# XC6SLX09-2FTG256C.net
KiCad netlist of a schematic drawn in Altium Designer
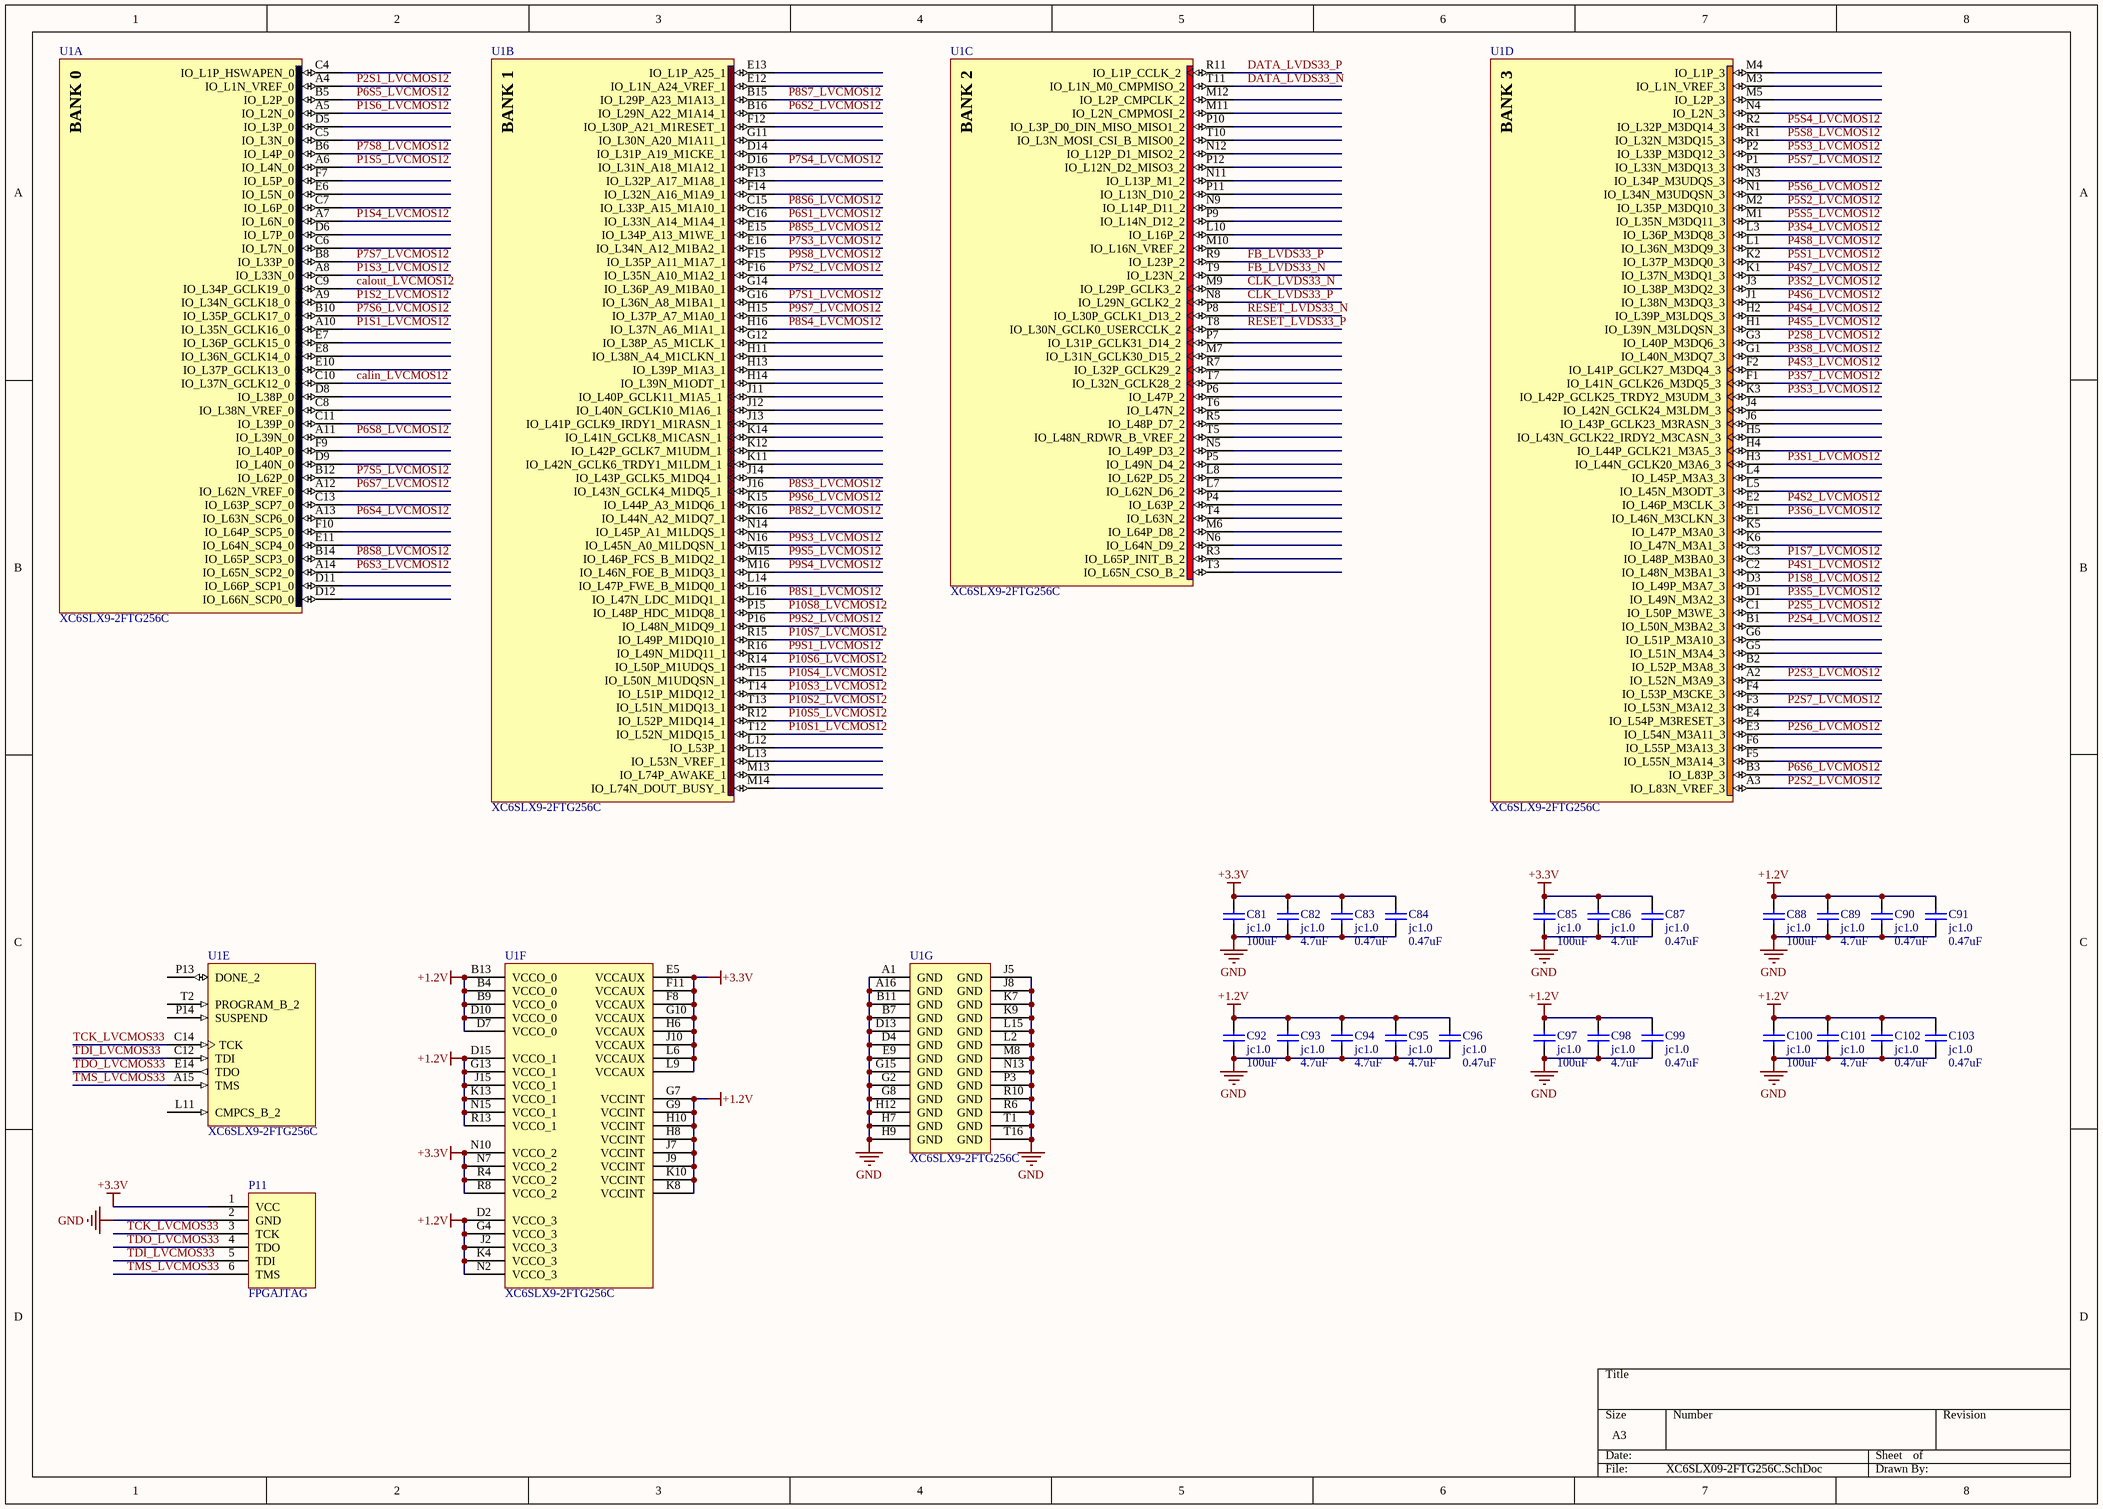
[diagram p0: XC6SLX09-2FTG256C.SchDoc]

(export (version "E")
  (design (tool "Eeschema 10.0.6"))
  (components
    (comp (ref "C81")
      (value "jc1.0")
      (footprint "0805")
      (description "Capacitor")
      (fields (field (name "ALTIUM_VALUE") "100uF") (field (name "PUBLISHER") "Altium Limited"))
      (libsource (lib "LIB01DXP2006SchLib") (part "Cap"))
    )
    (comp (ref "C82")
      (value "jc1.0")
      (footprint "0402")
      (description "Capacitor")
      (fields (field (name "ALTIUM_VALUE") "4.7uF") (field (name "PUBLISHER") "Altium Limited"))
      (libsource (lib "LIB01DXP2006SchLib") (part "Cap"))
    )
    (comp (ref "C83")
      (value "jc1.0")
      (footprint "0402")
      (description "Capacitor")
      (fields (field (name "ALTIUM_VALUE") "0.47uF") (field (name "PUBLISHER") "Altium Limited"))
      (libsource (lib "LIB01DXP2006SchLib") (part "Cap"))
    )
    (comp (ref "C84")
      (value "jc1.0")
      (footprint "0402")
      (description "Capacitor")
      (fields (field (name "ALTIUM_VALUE") "0.47uF") (field (name "PUBLISHER") "Altium Limited"))
      (libsource (lib "LIB01DXP2006SchLib") (part "Cap"))
    )
    (comp (ref "C85")
      (value "jc1.0")
      (footprint "0805")
      (description "Capacitor")
      (fields (field (name "ALTIUM_VALUE") "100uF") (field (name "PUBLISHER") "Altium Limited"))
      (libsource (lib "LIB01DXP2006SchLib") (part "Cap"))
    )
    (comp (ref "C86")
      (value "jc1.0")
      (footprint "0402")
      (description "Capacitor")
      (fields (field (name "ALTIUM_VALUE") "4.7uF") (field (name "PUBLISHER") "Altium Limited"))
      (libsource (lib "LIB01DXP2006SchLib") (part "Cap"))
    )
    (comp (ref "C87")
      (value "jc1.0")
      (footprint "0402")
      (description "Capacitor")
      (fields (field (name "ALTIUM_VALUE") "0.47uF") (field (name "PUBLISHER") "Altium Limited"))
      (libsource (lib "LIB01DXP2006SchLib") (part "Cap"))
    )
    (comp (ref "C88")
      (value "jc1.0")
      (footprint "0805")
      (description "Capacitor")
      (fields (field (name "ALTIUM_VALUE") "100uF") (field (name "PUBLISHER") "Altium Limited"))
      (libsource (lib "LIB01DXP2006SchLib") (part "Cap"))
    )
    (comp (ref "C89")
      (value "jc1.0")
      (footprint "0402")
      (description "Capacitor")
      (fields (field (name "ALTIUM_VALUE") "4.7uF") (field (name "PUBLISHER") "Altium Limited"))
      (libsource (lib "LIB01DXP2006SchLib") (part "Cap"))
    )
    (comp (ref "C90")
      (value "jc1.0")
      (footprint "0402")
      (description "Capacitor")
      (fields (field (name "ALTIUM_VALUE") "0.47uF") (field (name "PUBLISHER") "Altium Limited"))
      (libsource (lib "LIB01DXP2006SchLib") (part "Cap"))
    )
    (comp (ref "C91")
      (value "jc1.0")
      (footprint "0402")
      (description "Capacitor")
      (fields (field (name "ALTIUM_VALUE") "0.47uF") (field (name "PUBLISHER") "Altium Limited"))
      (libsource (lib "LIB01DXP2006SchLib") (part "Cap"))
    )
    (comp (ref "C92")
      (value "jc1.0")
      (footprint "0805")
      (description "Capacitor")
      (fields (field (name "ALTIUM_VALUE") "100uF") (field (name "PUBLISHER") "Altium Limited"))
      (libsource (lib "LIB01DXP2006SchLib") (part "Cap"))
    )
    (comp (ref "C93")
      (value "jc1.0")
      (footprint "0402")
      (description "Capacitor")
      (fields (field (name "ALTIUM_VALUE") "4.7uF") (field (name "PUBLISHER") "Altium Limited"))
      (libsource (lib "LIB01DXP2006SchLib") (part "Cap"))
    )
    (comp (ref "C94")
      (value "jc1.0")
      (footprint "0402")
      (description "Capacitor")
      (fields (field (name "ALTIUM_VALUE") "4.7uF") (field (name "PUBLISHER") "Altium Limited"))
      (libsource (lib "LIB01DXP2006SchLib") (part "Cap"))
    )
    (comp (ref "C95")
      (value "jc1.0")
      (footprint "0402")
      (description "Capacitor")
      (fields (field (name "ALTIUM_VALUE") "4.7uF") (field (name "PUBLISHER") "Altium Limited"))
      (libsource (lib "LIB01DXP2006SchLib") (part "Cap"))
    )
    (comp (ref "C96")
      (value "jc1.0")
      (footprint "0402")
      (description "Capacitor")
      (fields (field (name "ALTIUM_VALUE") "0.47uF") (field (name "PUBLISHER") "Altium Limited"))
      (libsource (lib "LIB01DXP2006SchLib") (part "Cap"))
    )
    (comp (ref "C97")
      (value "jc1.0")
      (footprint "0805")
      (description "Capacitor")
      (fields (field (name "ALTIUM_VALUE") "100uF") (field (name "PUBLISHER") "Altium Limited"))
      (libsource (lib "LIB01DXP2006SchLib") (part "Cap"))
    )
    (comp (ref "C98")
      (value "jc1.0")
      (footprint "0402")
      (description "Capacitor")
      (fields (field (name "ALTIUM_VALUE") "4.7uF") (field (name "PUBLISHER") "Altium Limited"))
      (libsource (lib "LIB01DXP2006SchLib") (part "Cap"))
    )
    (comp (ref "C99")
      (value "jc1.0")
      (footprint "0402")
      (description "Capacitor")
      (fields (field (name "ALTIUM_VALUE") "0.47uF") (field (name "PUBLISHER") "Altium Limited"))
      (libsource (lib "LIB01DXP2006SchLib") (part "Cap"))
    )
    (comp (ref "C100")
      (value "jc1.0")
      (footprint "0805")
      (description "Capacitor")
      (fields (field (name "ALTIUM_VALUE") "100uF") (field (name "PUBLISHER") "Altium Limited"))
      (libsource (lib "LIB01DXP2006SchLib") (part "Cap"))
    )
    (comp (ref "C101")
      (value "jc1.0")
      (footprint "0402")
      (description "Capacitor")
      (fields (field (name "ALTIUM_VALUE") "4.7uF") (field (name "PUBLISHER") "Altium Limited"))
      (libsource (lib "LIB01DXP2006SchLib") (part "Cap"))
    )
    (comp (ref "C102")
      (value "jc1.0")
      (footprint "0402")
      (description "Capacitor")
      (fields (field (name "ALTIUM_VALUE") "0.47uF") (field (name "PUBLISHER") "Altium Limited"))
      (libsource (lib "LIB01DXP2006SchLib") (part "Cap"))
    )
    (comp (ref "C103")
      (value "jc1.0")
      (footprint "0402")
      (description "Capacitor")
      (fields (field (name "ALTIUM_VALUE") "0.47uF") (field (name "PUBLISHER") "Altium Limited"))
      (libsource (lib "LIB01DXP2006SchLib") (part "Cap"))
    )
    (comp (ref "P11")
      (value "FPGAJTAG")
      (footprint "SIP6")
      (libsource (lib "LIB01DXP2006SchLib") (part "FPGAJTAGHEADER"))
    )
    (comp (ref "U1")
      (value "XC6SLX9-2FTG256C")
      (footprint "FTG256")
      (libsource (lib "Spartan-6") (part "XC6SLX9-2FTG256C"))
    )
  )
  (nets
    (net (code "1") (name "+1.2V") (class "Default")
      (node (ref "C100") (pin "2") (pinfunction "2_2") (pintype "passive"))
      (node (ref "C101") (pin "2") (pinfunction "2_2") (pintype "passive"))
      (node (ref "C102") (pin "2") (pinfunction "2_2") (pintype "passive"))
      (node (ref "C103") (pin "2") (pinfunction "2_2") (pintype "passive"))
      (node (ref "C88") (pin "2") (pinfunction "2_2") (pintype "passive"))
      (node (ref "C89") (pin "2") (pinfunction "2_2") (pintype "passive"))
      (node (ref "C90") (pin "2") (pinfunction "2_2") (pintype "passive"))
      (node (ref "C91") (pin "2") (pinfunction "2_2") (pintype "passive"))
      (node (ref "C92") (pin "2") (pinfunction "2_2") (pintype "passive"))
      (node (ref "C93") (pin "2") (pinfunction "2_2") (pintype "passive"))
      (node (ref "C94") (pin "2") (pinfunction "2_2") (pintype "passive"))
      (node (ref "C95") (pin "2") (pinfunction "2_2") (pintype "passive"))
      (node (ref "C96") (pin "2") (pinfunction "2_2") (pintype "passive"))
      (node (ref "C97") (pin "2") (pinfunction "2_2") (pintype "passive"))
      (node (ref "C98") (pin "2") (pinfunction "2_2") (pintype "passive"))
      (node (ref "C99") (pin "2") (pinfunction "2_2") (pintype "passive"))
      (node (ref "U1") (pin "B13") (pinfunction "VCCO_0_B13") (pintype "power_in"))
      (node (ref "U1") (pin "B4") (pinfunction "VCCO_0_B4") (pintype "power_in"))
      (node (ref "U1") (pin "B9") (pinfunction "VCCO_0_B9") (pintype "power_in"))
      (node (ref "U1") (pin "D10") (pinfunction "VCCO_0_D10") (pintype "power_in"))
      (node (ref "U1") (pin "D15") (pinfunction "VCCO_1_D15") (pintype "power_in"))
      (node (ref "U1") (pin "D2") (pinfunction "VCCO_3_D2") (pintype "power_in"))
      (node (ref "U1") (pin "D7") (pinfunction "VCCO_0_D7") (pintype "power_in"))
      (node (ref "U1") (pin "G13") (pinfunction "VCCO_1_G13") (pintype "power_in"))
      (node (ref "U1") (pin "G4") (pinfunction "VCCO_3_G4") (pintype "power_in"))
      (node (ref "U1") (pin "G7") (pinfunction "VCCINT_G7") (pintype "power_in"))
      (node (ref "U1") (pin "G9") (pinfunction "VCCINT_G9") (pintype "power_in"))
      (node (ref "U1") (pin "H10") (pinfunction "VCCINT_H10") (pintype "power_in"))
      (node (ref "U1") (pin "H8") (pinfunction "VCCINT_H8") (pintype "power_in"))
      (node (ref "U1") (pin "J15") (pinfunction "VCCO_1_J15") (pintype "power_in"))
      (node (ref "U1") (pin "J2") (pinfunction "VCCO_3_J2") (pintype "power_in"))
      (node (ref "U1") (pin "J7") (pinfunction "VCCINT_J7") (pintype "power_in"))
      (node (ref "U1") (pin "J9") (pinfunction "VCCINT_J9") (pintype "power_in"))
      (node (ref "U1") (pin "K10") (pinfunction "VCCINT_K10") (pintype "power_in"))
      (node (ref "U1") (pin "K13") (pinfunction "VCCO_1_K13") (pintype "power_in"))
      (node (ref "U1") (pin "K4") (pinfunction "VCCO_3_K4") (pintype "power_in"))
      (node (ref "U1") (pin "K8") (pinfunction "VCCINT_K8") (pintype "power_in"))
      (node (ref "U1") (pin "N15") (pinfunction "VCCO_1_N15") (pintype "power_in"))
      (node (ref "U1") (pin "N2") (pinfunction "VCCO_3_N2") (pintype "power_in"))
      (node (ref "U1") (pin "R13") (pinfunction "VCCO_1_R13") (pintype "power_in"))
    )
    (net (code "2") (name "+3.3V") (class "Default")
      (node (ref "C81") (pin "2") (pinfunction "2_2") (pintype "passive"))
      (node (ref "C82") (pin "2") (pinfunction "2_2") (pintype "passive"))
      (node (ref "C83") (pin "2") (pinfunction "2_2") (pintype "passive"))
      (node (ref "C84") (pin "2") (pinfunction "2_2") (pintype "passive"))
      (node (ref "C85") (pin "2") (pinfunction "2_2") (pintype "passive"))
      (node (ref "C86") (pin "2") (pinfunction "2_2") (pintype "passive"))
      (node (ref "C87") (pin "2") (pinfunction "2_2") (pintype "passive"))
      (node (ref "P11") (pin "1") (pinfunction "VCC_1") (pintype "passive"))
      (node (ref "U1") (pin "E5") (pinfunction "VCCAUX_E5") (pintype "power_in"))
      (node (ref "U1") (pin "F11") (pinfunction "VCCAUX_F11") (pintype "power_in"))
      (node (ref "U1") (pin "F8") (pinfunction "VCCAUX_F8") (pintype "power_in"))
      (node (ref "U1") (pin "G10") (pinfunction "VCCAUX_G10") (pintype "power_in"))
      (node (ref "U1") (pin "H6") (pinfunction "VCCAUX_H6") (pintype "power_in"))
      (node (ref "U1") (pin "J10") (pinfunction "VCCAUX_J10") (pintype "power_in"))
      (node (ref "U1") (pin "L6") (pinfunction "VCCAUX_L6") (pintype "power_in"))
      (node (ref "U1") (pin "L9") (pinfunction "VCCAUX_L9") (pintype "power_in"))
      (node (ref "U1") (pin "N10") (pinfunction "VCCO_2_N10") (pintype "power_in"))
      (node (ref "U1") (pin "N7") (pinfunction "VCCO_2_N7") (pintype "power_in"))
      (node (ref "U1") (pin "R4") (pinfunction "VCCO_2_R4") (pintype "power_in"))
      (node (ref "U1") (pin "R8") (pinfunction "VCCO_2_R8") (pintype "power_in"))
    )
    (net (code "3") (name "/CLK_LVDS33_N") (class "Default")
      (node (ref "U1") (pin "M9") (pinfunction "IO_L29P_GCLK3_2_M9") (pintype "bidirectional"))
    )
    (net (code "4") (name "/CLK_LVDS33_P") (class "Default")
      (node (ref "U1") (pin "N8") (pinfunction "IO_L29N_GCLK2_2_N8") (pintype "bidirectional"))
    )
    (net (code "5") (name "/DATA_LVDS33_N") (class "Default")
      (node (ref "U1") (pin "T11") (pinfunction "IO_L1N_M0_CMPMISO_2_T11") (pintype "bidirectional"))
    )
    (net (code "6") (name "/DATA_LVDS33_P") (class "Default")
      (node (ref "U1") (pin "R11") (pinfunction "IO_L1P_CCLK_2_R11") (pintype "bidirectional"))
    )
    (net (code "7") (name "/FB_LVDS33_N") (class "Default")
      (node (ref "U1") (pin "T9") (pinfunction "IO_L23N_2_T9") (pintype "bidirectional"))
    )
    (net (code "8") (name "/FB_LVDS33_P") (class "Default")
      (node (ref "U1") (pin "R9") (pinfunction "IO_L23P_2_R9") (pintype "bidirectional"))
    )
    (net (code "9") (name "/P1S1_LVCMOS12") (class "Default")
      (node (ref "U1") (pin "A10") (pinfunction "IO_L35N_GCLK16_0_A10") (pintype "bidirectional"))
    )
    (net (code "10") (name "/P1S2_LVCMOS12") (class "Default")
      (node (ref "U1") (pin "A9") (pinfunction "IO_L34N_GCLK18_0_A9") (pintype "bidirectional"))
    )
    (net (code "11") (name "/P1S3_LVCMOS12") (class "Default")
      (node (ref "U1") (pin "A8") (pinfunction "IO_L33N_0_A8") (pintype "bidirectional"))
    )
    (net (code "12") (name "/P1S4_LVCMOS12") (class "Default")
      (node (ref "U1") (pin "A7") (pinfunction "IO_L6N_0_A7") (pintype "bidirectional"))
    )
    (net (code "13") (name "/P1S5_LVCMOS12") (class "Default")
      (node (ref "U1") (pin "A6") (pinfunction "IO_L4N_0_A6") (pintype "bidirectional"))
    )
    (net (code "14") (name "/P1S6_LVCMOS12") (class "Default")
      (node (ref "U1") (pin "A5") (pinfunction "IO_L2N_0_A5") (pintype "bidirectional"))
    )
    (net (code "15") (name "/P1S7_LVCMOS12") (class "Default")
      (node (ref "U1") (pin "C3") (pinfunction "IO_L48P_M3BA0_3_C3") (pintype "bidirectional"))
    )
    (net (code "16") (name "/P1S8_LVCMOS12") (class "Default")
      (node (ref "U1") (pin "D3") (pinfunction "IO_L49P_M3A7_3_D3") (pintype "bidirectional"))
    )
    (net (code "17") (name "/P2S1_LVCMOS12") (class "Default")
      (node (ref "U1") (pin "A4") (pinfunction "IO_L1N_VREF_0_A4") (pintype "bidirectional"))
    )
    (net (code "18") (name "/P2S2_LVCMOS12") (class "Default")
      (node (ref "U1") (pin "A3") (pinfunction "IO_L83N_VREF_3_A3") (pintype "bidirectional"))
    )
    (net (code "19") (name "/P2S3_LVCMOS12") (class "Default")
      (node (ref "U1") (pin "A2") (pinfunction "IO_L52N_M3A9_3_A2") (pintype "bidirectional"))
    )
    (net (code "20") (name "/P2S4_LVCMOS12") (class "Default")
      (node (ref "U1") (pin "B1") (pinfunction "IO_L50N_M3BA2_3_B1") (pintype "bidirectional"))
    )
    (net (code "21") (name "/P2S5_LVCMOS12") (class "Default")
      (node (ref "U1") (pin "C1") (pinfunction "IO_L50P_M3WE_3_C1") (pintype "bidirectional"))
    )
    (net (code "22") (name "/P2S6_LVCMOS12") (class "Default")
      (node (ref "U1") (pin "E3") (pinfunction "IO_L54N_M3A11_3_E3") (pintype "bidirectional"))
    )
    (net (code "23") (name "/P2S7_LVCMOS12") (class "Default")
      (node (ref "U1") (pin "F3") (pinfunction "IO_L53N_M3A12_3_F3") (pintype "bidirectional"))
    )
    (net (code "24") (name "/P2S8_LVCMOS12") (class "Default")
      (node (ref "U1") (pin "G3") (pinfunction "IO_L40P_M3DQ6_3_G3") (pintype "bidirectional"))
    )
    (net (code "25") (name "/P3S1_LVCMOS12") (class "Default")
      (node (ref "U1") (pin "H3") (pinfunction "IO_L44N_GCLK20_M3A6_3_H3") (pintype "bidirectional"))
    )
    (net (code "26") (name "/P3S2_LVCMOS12") (class "Default")
      (node (ref "U1") (pin "J3") (pinfunction "IO_L38P_M3DQ2_3_J3") (pintype "bidirectional"))
    )
    (net (code "27") (name "/P3S3_LVCMOS12") (class "Default")
      (node (ref "U1") (pin "K3") (pinfunction "IO_L42P_GCLK25_TRDY2_M3UDM_3_K3") (pintype "bidirectional"))
    )
    (net (code "28") (name "/P3S4_LVCMOS12") (class "Default")
      (node (ref "U1") (pin "L3") (pinfunction "IO_L36P_M3DQ8_3_L3") (pintype "bidirectional"))
    )
    (net (code "29") (name "/P3S5_LVCMOS12") (class "Default")
      (node (ref "U1") (pin "D1") (pinfunction "IO_L49N_M3A2_3_D1") (pintype "bidirectional"))
    )
    (net (code "30") (name "/P3S6_LVCMOS12") (class "Default")
      (node (ref "U1") (pin "E1") (pinfunction "IO_L46N_M3CLKN_3_E1") (pintype "bidirectional"))
    )
    (net (code "31") (name "/P3S7_LVCMOS12") (class "Default")
      (node (ref "U1") (pin "F1") (pinfunction "IO_L41N_GCLK26_M3DQ5_3_F1") (pintype "bidirectional"))
    )
    (net (code "32") (name "/P3S8_LVCMOS12") (class "Default")
      (node (ref "U1") (pin "G1") (pinfunction "IO_L40N_M3DQ7_3_G1") (pintype "bidirectional"))
    )
    (net (code "33") (name "/P4S1_LVCMOS12") (class "Default")
      (node (ref "U1") (pin "C2") (pinfunction "IO_L48N_M3BA1_3_C2") (pintype "bidirectional"))
    )
    (net (code "34") (name "/P4S2_LVCMOS12") (class "Default")
      (node (ref "U1") (pin "E2") (pinfunction "IO_L46P_M3CLK_3_E2") (pintype "bidirectional"))
    )
    (net (code "35") (name "/P4S3_LVCMOS12") (class "Default")
      (node (ref "U1") (pin "F2") (pinfunction "IO_L41P_GCLK27_M3DQ4_3_F2") (pintype "bidirectional"))
    )
    (net (code "36") (name "/P4S4_LVCMOS12") (class "Default")
      (node (ref "U1") (pin "H2") (pinfunction "IO_L39P_M3LDQS_3_H2") (pintype "bidirectional"))
    )
    (net (code "37") (name "/P4S5_LVCMOS12") (class "Default")
      (node (ref "U1") (pin "H1") (pinfunction "IO_L39N_M3LDQSN_3_H1") (pintype "bidirectional"))
    )
    (net (code "38") (name "/P4S6_LVCMOS12") (class "Default")
      (node (ref "U1") (pin "J1") (pinfunction "IO_L38N_M3DQ3_3_J1") (pintype "bidirectional"))
    )
    (net (code "39") (name "/P4S7_LVCMOS12") (class "Default")
      (node (ref "U1") (pin "K1") (pinfunction "IO_L37N_M3DQ1_3_K1") (pintype "bidirectional"))
    )
    (net (code "40") (name "/P4S8_LVCMOS12") (class "Default")
      (node (ref "U1") (pin "L1") (pinfunction "IO_L36N_M3DQ9_3_L1") (pintype "bidirectional"))
    )
    (net (code "41") (name "/P5S1_LVCMOS12") (class "Default")
      (node (ref "U1") (pin "K2") (pinfunction "IO_L37P_M3DQ0_3_K2") (pintype "bidirectional"))
    )
    (net (code "42") (name "/P5S2_LVCMOS12") (class "Default")
      (node (ref "U1") (pin "M2") (pinfunction "IO_L35P_M3DQ10_3_M2") (pintype "bidirectional"))
    )
    (net (code "43") (name "/P5S3_LVCMOS12") (class "Default")
      (node (ref "U1") (pin "P2") (pinfunction "IO_L33P_M3DQ12_3_P2") (pintype "bidirectional"))
    )
    (net (code "44") (name "/P5S4_LVCMOS12") (class "Default")
      (node (ref "U1") (pin "R2") (pinfunction "IO_L32P_M3DQ14_3_R2") (pintype "bidirectional"))
    )
    (net (code "45") (name "/P5S5_LVCMOS12") (class "Default")
      (node (ref "U1") (pin "M1") (pinfunction "IO_L35N_M3DQ11_3_M1") (pintype "bidirectional"))
    )
    (net (code "46") (name "/P5S6_LVCMOS12") (class "Default")
      (node (ref "U1") (pin "N1") (pinfunction "IO_L34N_M3UDQSN_3_N1") (pintype "bidirectional"))
    )
    (net (code "47") (name "/P5S7_LVCMOS12") (class "Default")
      (node (ref "U1") (pin "P1") (pinfunction "IO_L33N_M3DQ13_3_P1") (pintype "bidirectional"))
    )
    (net (code "48") (name "/P5S8_LVCMOS12") (class "Default")
      (node (ref "U1") (pin "R1") (pinfunction "IO_L32N_M3DQ15_3_R1") (pintype "bidirectional"))
    )
    (net (code "49") (name "/P6S1_LVCMOS12") (class "Default")
      (node (ref "U1") (pin "C16") (pinfunction "IO_L33N_A14_M1A4_1_C16") (pintype "bidirectional"))
    )
    (net (code "50") (name "/P6S2_LVCMOS12") (class "Default")
      (node (ref "U1") (pin "B16") (pinfunction "IO_L29N_A22_M1A14_1_B16") (pintype "bidirectional"))
    )
    (net (code "51") (name "/P6S3_LVCMOS12") (class "Default")
      (node (ref "U1") (pin "A14") (pinfunction "IO_L65N_SCP2_0_A14") (pintype "bidirectional"))
    )
    (net (code "52") (name "/P6S4_LVCMOS12") (class "Default")
      (node (ref "U1") (pin "A13") (pinfunction "IO_L63N_SCP6_0_A13") (pintype "bidirectional"))
    )
    (net (code "53") (name "/P6S5_LVCMOS12") (class "Default")
      (node (ref "U1") (pin "B5") (pinfunction "IO_L2P_0_B5") (pintype "bidirectional"))
    )
    (net (code "54") (name "/P6S6_LVCMOS12") (class "Default")
      (node (ref "U1") (pin "B3") (pinfunction "IO_L83P_3_B3") (pintype "bidirectional"))
    )
    (net (code "55") (name "/P6S7_LVCMOS12") (class "Default")
      (node (ref "U1") (pin "A12") (pinfunction "IO_L62N_VREF_0_A12") (pintype "bidirectional"))
    )
    (net (code "56") (name "/P6S8_LVCMOS12") (class "Default")
      (node (ref "U1") (pin "A11") (pinfunction "IO_L39N_0_A11") (pintype "bidirectional"))
    )
    (net (code "57") (name "/P7S1_LVCMOS12") (class "Default")
      (node (ref "U1") (pin "G16") (pinfunction "IO_L36N_A8_M1BA1_1_G16") (pintype "bidirectional"))
    )
    (net (code "58") (name "/P7S2_LVCMOS12") (class "Default")
      (node (ref "U1") (pin "F16") (pinfunction "IO_L35N_A10_M1A2_1_F16") (pintype "bidirectional"))
    )
    (net (code "59") (name "/P7S3_LVCMOS12") (class "Default")
      (node (ref "U1") (pin "E16") (pinfunction "IO_L34N_A12_M1BA2_1_E16") (pintype "bidirectional"))
    )
    (net (code "60") (name "/P7S4_LVCMOS12") (class "Default")
      (node (ref "U1") (pin "D16") (pinfunction "IO_L31N_A18_M1A12_1_D16") (pintype "bidirectional"))
    )
    (net (code "61") (name "/P7S5_LVCMOS12") (class "Default")
      (node (ref "U1") (pin "B12") (pinfunction "IO_L62P_0_B12") (pintype "bidirectional"))
    )
    (net (code "62") (name "/P7S6_LVCMOS12") (class "Default")
      (node (ref "U1") (pin "B10") (pinfunction "IO_L35P_GCLK17_0_B10") (pintype "bidirectional"))
    )
    (net (code "63") (name "/P7S7_LVCMOS12") (class "Default")
      (node (ref "U1") (pin "B8") (pinfunction "IO_L33P_0_B8") (pintype "bidirectional"))
    )
    (net (code "64") (name "/P7S8_LVCMOS12") (class "Default")
      (node (ref "U1") (pin "B6") (pinfunction "IO_L4P_0_B6") (pintype "bidirectional"))
    )
    (net (code "65") (name "/P8S1_LVCMOS12") (class "Default")
      (node (ref "U1") (pin "L16") (pinfunction "IO_L47N_LDC_M1DQ1_1_L16") (pintype "bidirectional"))
    )
    (net (code "66") (name "/P8S2_LVCMOS12") (class "Default")
      (node (ref "U1") (pin "K16") (pinfunction "IO_L44N_A2_M1DQ7_1_K16") (pintype "bidirectional"))
    )
    (net (code "67") (name "/P8S3_LVCMOS12") (class "Default")
      (node (ref "U1") (pin "J16") (pinfunction "IO_L43N_GCLK4_M1DQ5_1_J16") (pintype "bidirectional"))
    )
    (net (code "68") (name "/P8S4_LVCMOS12") (class "Default")
      (node (ref "U1") (pin "H16") (pinfunction "IO_L37N_A6_M1A1_1_H16") (pintype "bidirectional"))
    )
    (net (code "69") (name "/P8S5_LVCMOS12") (class "Default")
      (node (ref "U1") (pin "E15") (pinfunction "IO_L34P_A13_M1WE_1_E15") (pintype "bidirectional"))
    )
    (net (code "70") (name "/P8S6_LVCMOS12") (class "Default")
      (node (ref "U1") (pin "C15") (pinfunction "IO_L33P_A15_M1A10_1_C15") (pintype "bidirectional"))
    )
    (net (code "71") (name "/P8S7_LVCMOS12") (class "Default")
      (node (ref "U1") (pin "B15") (pinfunction "IO_L29P_A23_M1A13_1_B15") (pintype "bidirectional"))
    )
    (net (code "72") (name "/P8S8_LVCMOS12") (class "Default")
      (node (ref "U1") (pin "B14") (pinfunction "IO_L65P_SCP3_0_B14") (pintype "bidirectional"))
    )
    (net (code "73") (name "/P9S1_LVCMOS12") (class "Default")
      (node (ref "U1") (pin "R16") (pinfunction "IO_L49N_M1DQ11_1_R16") (pintype "bidirectional"))
    )
    (net (code "74") (name "/P9S2_LVCMOS12") (class "Default")
      (node (ref "U1") (pin "P16") (pinfunction "IO_L48N_M1DQ9_1_P16") (pintype "bidirectional"))
    )
    (net (code "75") (name "/P9S3_LVCMOS12") (class "Default")
      (node (ref "U1") (pin "N16") (pinfunction "IO_L45N_A0_M1LDQSN_1_N16") (pintype "bidirectional"))
    )
    (net (code "76") (name "/P9S4_LVCMOS12") (class "Default")
      (node (ref "U1") (pin "M16") (pinfunction "IO_L46N_FOE_B_M1DQ3_1_M16") (pintype "bidirectional"))
    )
    (net (code "77") (name "/P9S5_LVCMOS12") (class "Default")
      (node (ref "U1") (pin "M15") (pinfunction "IO_L46P_FCS_B_M1DQ2_1_M15") (pintype "bidirectional"))
    )
    (net (code "78") (name "/P9S6_LVCMOS12") (class "Default")
      (node (ref "U1") (pin "K15") (pinfunction "IO_L44P_A3_M1DQ6_1_K15") (pintype "bidirectional"))
    )
    (net (code "79") (name "/P9S7_LVCMOS12") (class "Default")
      (node (ref "U1") (pin "H15") (pinfunction "IO_L37P_A7_M1A0_1_H15") (pintype "bidirectional"))
    )
    (net (code "80") (name "/P9S8_LVCMOS12") (class "Default")
      (node (ref "U1") (pin "F15") (pinfunction "IO_L35P_A11_M1A7_1_F15") (pintype "bidirectional"))
    )
    (net (code "81") (name "/P10S1_LVCMOS12") (class "Default")
      (node (ref "U1") (pin "T12") (pinfunction "IO_L52N_M1DQ15_1_T12") (pintype "bidirectional"))
    )
    (net (code "82") (name "/P10S2_LVCMOS12") (class "Default")
      (node (ref "U1") (pin "T13") (pinfunction "IO_L51N_M1DQ13_1_T13") (pintype "bidirectional"))
    )
    (net (code "83") (name "/P10S3_LVCMOS12") (class "Default")
      (node (ref "U1") (pin "T14") (pinfunction "IO_L51P_M1DQ12_1_T14") (pintype "bidirectional"))
    )
    (net (code "84") (name "/P10S4_LVCMOS12") (class "Default")
      (node (ref "U1") (pin "T15") (pinfunction "IO_L50N_M1UDQSN_1_T15") (pintype "bidirectional"))
    )
    (net (code "85") (name "/P10S5_LVCMOS12") (class "Default")
      (node (ref "U1") (pin "R12") (pinfunction "IO_L52P_M1DQ14_1_R12") (pintype "bidirectional"))
    )
    (net (code "86") (name "/P10S6_LVCMOS12") (class "Default")
      (node (ref "U1") (pin "R14") (pinfunction "IO_L50P_M1UDQS_1_R14") (pintype "bidirectional"))
    )
    (net (code "87") (name "/P10S7_LVCMOS12") (class "Default")
      (node (ref "U1") (pin "R15") (pinfunction "IO_L49P_M1DQ10_1_R15") (pintype "bidirectional"))
    )
    (net (code "88") (name "/P10S8_LVCMOS12") (class "Default")
      (node (ref "U1") (pin "P15") (pinfunction "IO_L48P_HDC_M1DQ8_1_P15") (pintype "bidirectional"))
    )
    (net (code "89") (name "/RESET_LVDS33_N") (class "Default")
      (node (ref "U1") (pin "P8") (pinfunction "IO_L30P_GCLK1_D13_2_P8") (pintype "bidirectional"))
    )
    (net (code "90") (name "/RESET_LVDS33_P") (class "Default")
      (node (ref "U1") (pin "T8") (pinfunction "IO_L30N_GCLK0_USERCCLK_2_T8") (pintype "bidirectional"))
    )
    (net (code "91") (name "/TCK_LVCMOS33") (class "Default")
      (node (ref "P11") (pin "3") (pinfunction "TCK_3") (pintype "passive"))
      (node (ref "U1") (pin "C14") (pinfunction "TCK_C14") (pintype "input"))
    )
    (net (code "92") (name "/TDI_LVCMOS33") (class "Default")
      (node (ref "P11") (pin "5") (pinfunction "TDI_5") (pintype "passive"))
      (node (ref "U1") (pin "C12") (pinfunction "TDI_C12") (pintype "input"))
    )
    (net (code "93") (name "/TDO_LVCMOS33") (class "Default")
      (node (ref "P11") (pin "4") (pinfunction "TDO_4") (pintype "passive"))
      (node (ref "U1") (pin "E14") (pinfunction "TDO_E14") (pintype "output"))
    )
    (net (code "94") (name "/TMS_LVCMOS33") (class "Default")
      (node (ref "P11") (pin "6") (pinfunction "TMS_6") (pintype "passive"))
      (node (ref "U1") (pin "A15") (pinfunction "TMS_A15") (pintype "input"))
    )
    (net (code "95") (name "/calin_LVCMOS12") (class "Default")
      (node (ref "U1") (pin "C10") (pinfunction "IO_L37N_GCLK12_0_C10") (pintype "bidirectional"))
    )
    (net (code "96") (name "/calout_LVCMOS12") (class "Default")
      (node (ref "U1") (pin "C9") (pinfunction "IO_L34P_GCLK19_0_C9") (pintype "bidirectional"))
    )
    (net (code "97") (name "GND") (class "Default")
      (node (ref "C100") (pin "1") (pinfunction "1_1") (pintype "passive"))
      (node (ref "C101") (pin "1") (pinfunction "1_1") (pintype "passive"))
      (node (ref "C102") (pin "1") (pinfunction "1_1") (pintype "passive"))
      (node (ref "C103") (pin "1") (pinfunction "1_1") (pintype "passive"))
      (node (ref "C81") (pin "1") (pinfunction "1_1") (pintype "passive"))
      (node (ref "C82") (pin "1") (pinfunction "1_1") (pintype "passive"))
      (node (ref "C83") (pin "1") (pinfunction "1_1") (pintype "passive"))
      (node (ref "C84") (pin "1") (pinfunction "1_1") (pintype "passive"))
      (node (ref "C85") (pin "1") (pinfunction "1_1") (pintype "passive"))
      (node (ref "C86") (pin "1") (pinfunction "1_1") (pintype "passive"))
      (node (ref "C87") (pin "1") (pinfunction "1_1") (pintype "passive"))
      (node (ref "C88") (pin "1") (pinfunction "1_1") (pintype "passive"))
      (node (ref "C89") (pin "1") (pinfunction "1_1") (pintype "passive"))
      (node (ref "C90") (pin "1") (pinfunction "1_1") (pintype "passive"))
      (node (ref "C91") (pin "1") (pinfunction "1_1") (pintype "passive"))
      (node (ref "C92") (pin "1") (pinfunction "1_1") (pintype "passive"))
      (node (ref "C93") (pin "1") (pinfunction "1_1") (pintype "passive"))
      (node (ref "C94") (pin "1") (pinfunction "1_1") (pintype "passive"))
      (node (ref "C95") (pin "1") (pinfunction "1_1") (pintype "passive"))
      (node (ref "C96") (pin "1") (pinfunction "1_1") (pintype "passive"))
      (node (ref "C97") (pin "1") (pinfunction "1_1") (pintype "passive"))
      (node (ref "C98") (pin "1") (pinfunction "1_1") (pintype "passive"))
      (node (ref "C99") (pin "1") (pinfunction "1_1") (pintype "passive"))
      (node (ref "P11") (pin "2") (pinfunction "GND_2") (pintype "passive"))
      (node (ref "U1") (pin "A1") (pinfunction "GND_A1") (pintype "power_in"))
      (node (ref "U1") (pin "A16") (pinfunction "GND_A16") (pintype "power_in"))
      (node (ref "U1") (pin "B11") (pinfunction "GND_B11") (pintype "power_in"))
      (node (ref "U1") (pin "B7") (pinfunction "GND_B7") (pintype "power_in"))
      (node (ref "U1") (pin "D13") (pinfunction "GND_D13") (pintype "power_in"))
      (node (ref "U1") (pin "D4") (pinfunction "GND_D4") (pintype "power_in"))
      (node (ref "U1") (pin "E9") (pinfunction "GND_E9") (pintype "power_in"))
      (node (ref "U1") (pin "G15") (pinfunction "GND_G15") (pintype "power_in"))
      (node (ref "U1") (pin "G2") (pinfunction "GND_G2") (pintype "power_in"))
      (node (ref "U1") (pin "G8") (pinfunction "GND_G8") (pintype "power_in"))
      (node (ref "U1") (pin "H12") (pinfunction "GND_H12") (pintype "power_in"))
      (node (ref "U1") (pin "H7") (pinfunction "GND_H7") (pintype "power_in"))
      (node (ref "U1") (pin "H9") (pinfunction "GND_H9") (pintype "power_in"))
      (node (ref "U1") (pin "J5") (pinfunction "GND_J5") (pintype "power_in"))
      (node (ref "U1") (pin "J8") (pinfunction "GND_J8") (pintype "power_in"))
      (node (ref "U1") (pin "K7") (pinfunction "GND_K7") (pintype "power_in"))
      (node (ref "U1") (pin "K9") (pinfunction "GND_K9") (pintype "power_in"))
      (node (ref "U1") (pin "L15") (pinfunction "GND_L15") (pintype "power_in"))
      (node (ref "U1") (pin "L2") (pinfunction "GND_L2") (pintype "power_in"))
      (node (ref "U1") (pin "M8") (pinfunction "GND_M8") (pintype "power_in"))
      (node (ref "U1") (pin "N13") (pinfunction "GND_N13") (pintype "power_in"))
      (node (ref "U1") (pin "P3") (pinfunction "GND_P3") (pintype "power_in"))
      (node (ref "U1") (pin "R10") (pinfunction "GND_R10") (pintype "power_in"))
      (node (ref "U1") (pin "R6") (pinfunction "GND_R6") (pintype "power_in"))
      (node (ref "U1") (pin "T1") (pinfunction "GND_T1") (pintype "power_in"))
      (node (ref "U1") (pin "T16") (pinfunction "GND_T16") (pintype "power_in"))
    )
    (net (code "98") (name "unconnected-(U1A-IO_L1P_HSWAPEN_0-PadC4)") (class "Default")
      (node (ref "U1") (pin "C4") (pinfunction "IO_L1P_HSWAPEN_0_C4") (pintype "bidirectional"))
    )
    (net (code "99") (name "unconnected-(U1A-IO_L3N_0-PadC5)") (class "Default")
      (node (ref "U1") (pin "C5") (pinfunction "IO_L3N_0_C5") (pintype "bidirectional"))
    )
    (net (code "100") (name "unconnected-(U1A-IO_L3P_0-PadD5)") (class "Default")
      (node (ref "U1") (pin "D5") (pinfunction "IO_L3P_0_D5") (pintype "bidirectional"))
    )
    (net (code "101") (name "unconnected-(U1A-IO_L5N_0-PadE6)") (class "Default")
      (node (ref "U1") (pin "E6") (pinfunction "IO_L5N_0_E6") (pintype "bidirectional"))
    )
    (net (code "102") (name "unconnected-(U1A-IO_L5P_0-PadF7)") (class "Default")
      (node (ref "U1") (pin "F7") (pinfunction "IO_L5P_0_F7") (pintype "bidirectional"))
    )
    (net (code "103") (name "unconnected-(U1A-IO_L6P_0-PadC7)") (class "Default")
      (node (ref "U1") (pin "C7") (pinfunction "IO_L6P_0_C7") (pintype "bidirectional"))
    )
    (net (code "104") (name "unconnected-(U1A-IO_L7N_0-PadC6)") (class "Default")
      (node (ref "U1") (pin "C6") (pinfunction "IO_L7N_0_C6") (pintype "bidirectional"))
    )
    (net (code "105") (name "unconnected-(U1A-IO_L7P_0-PadD6)") (class "Default")
      (node (ref "U1") (pin "D6") (pinfunction "IO_L7P_0_D6") (pintype "bidirectional"))
    )
    (net (code "106") (name "unconnected-(U1A-IO_L36N_GCLK14_0-PadE8)") (class "Default")
      (node (ref "U1") (pin "E8") (pinfunction "IO_L36N_GCLK14_0_E8") (pintype "bidirectional"))
    )
    (net (code "107") (name "unconnected-(U1A-IO_L36P_GCLK15_0-PadE7)") (class "Default")
      (node (ref "U1") (pin "E7") (pinfunction "IO_L36P_GCLK15_0_E7") (pintype "bidirectional"))
    )
    (net (code "108") (name "unconnected-(U1A-IO_L37P_GCLK13_0-PadE10)") (class "Default")
      (node (ref "U1") (pin "E10") (pinfunction "IO_L37P_GCLK13_0_E10") (pintype "bidirectional"))
    )
    (net (code "109") (name "unconnected-(U1A-IO_L38N_VREF_0-PadC8)") (class "Default")
      (node (ref "U1") (pin "C8") (pinfunction "IO_L38N_VREF_0_C8") (pintype "bidirectional"))
    )
    (net (code "110") (name "unconnected-(U1A-IO_L38P_0-PadD8)") (class "Default")
      (node (ref "U1") (pin "D8") (pinfunction "IO_L38P_0_D8") (pintype "bidirectional"))
    )
    (net (code "111") (name "unconnected-(U1A-IO_L39P_0-PadC11)") (class "Default")
      (node (ref "U1") (pin "C11") (pinfunction "IO_L39P_0_C11") (pintype "bidirectional"))
    )
    (net (code "112") (name "unconnected-(U1A-IO_L40N_0-PadD9)") (class "Default")
      (node (ref "U1") (pin "D9") (pinfunction "IO_L40N_0_D9") (pintype "bidirectional"))
    )
    (net (code "113") (name "unconnected-(U1A-IO_L40P_0-PadF9)") (class "Default")
      (node (ref "U1") (pin "F9") (pinfunction "IO_L40P_0_F9") (pintype "bidirectional"))
    )
    (net (code "114") (name "unconnected-(U1A-IO_L63P_SCP7_0-PadC13)") (class "Default")
      (node (ref "U1") (pin "C13") (pinfunction "IO_L63P_SCP7_0_C13") (pintype "bidirectional"))
    )
    (net (code "115") (name "unconnected-(U1A-IO_L64N_SCP4_0-PadE11)") (class "Default")
      (node (ref "U1") (pin "E11") (pinfunction "IO_L64N_SCP4_0_E11") (pintype "bidirectional"))
    )
    (net (code "116") (name "unconnected-(U1A-IO_L64P_SCP5_0-PadF10)") (class "Default")
      (node (ref "U1") (pin "F10") (pinfunction "IO_L64P_SCP5_0_F10") (pintype "bidirectional"))
    )
    (net (code "117") (name "unconnected-(U1A-IO_L66N_SCP0_0-PadD12)") (class "Default")
      (node (ref "U1") (pin "D12") (pinfunction "IO_L66N_SCP0_0_D12") (pintype "bidirectional"))
    )
    (net (code "118") (name "unconnected-(U1A-IO_L66P_SCP1_0-PadD11)") (class "Default")
      (node (ref "U1") (pin "D11") (pinfunction "IO_L66P_SCP1_0_D11") (pintype "bidirectional"))
    )
    (net (code "119") (name "unconnected-(U1B-IO_L1N_A24_VREF_1-PadE12)") (class "Default")
      (node (ref "U1") (pin "E12") (pinfunction "IO_L1N_A24_VREF_1_E12") (pintype "bidirectional"))
    )
    (net (code "120") (name "unconnected-(U1B-IO_L1P_A25_1-PadE13)") (class "Default")
      (node (ref "U1") (pin "E13") (pinfunction "IO_L1P_A25_1_E13") (pintype "bidirectional"))
    )
    (net (code "121") (name "unconnected-(U1B-IO_L30N_A20_M1A11_1-PadG11)") (class "Default")
      (node (ref "U1") (pin "G11") (pinfunction "IO_L30N_A20_M1A11_1_G11") (pintype "bidirectional"))
    )
    (net (code "122") (name "unconnected-(U1B-IO_L30P_A21_M1RESET_1-PadF12)") (class "Default")
      (node (ref "U1") (pin "F12") (pinfunction "IO_L30P_A21_M1RESET_1_F12") (pintype "bidirectional"))
    )
    (net (code "123") (name "unconnected-(U1B-IO_L31P_A19_M1CKE_1-PadD14)") (class "Default")
      (node (ref "U1") (pin "D14") (pinfunction "IO_L31P_A19_M1CKE_1_D14") (pintype "bidirectional"))
    )
    (net (code "124") (name "unconnected-(U1B-IO_L32N_A16_M1A9_1-PadF14)") (class "Default")
      (node (ref "U1") (pin "F14") (pinfunction "IO_L32N_A16_M1A9_1_F14") (pintype "bidirectional"))
    )
    (net (code "125") (name "unconnected-(U1B-IO_L32P_A17_M1A8_1-PadF13)") (class "Default")
      (node (ref "U1") (pin "F13") (pinfunction "IO_L32P_A17_M1A8_1_F13") (pintype "bidirectional"))
    )
    (net (code "126") (name "unconnected-(U1B-IO_L36P_A9_M1BA0_1-PadG14)") (class "Default")
      (node (ref "U1") (pin "G14") (pinfunction "IO_L36P_A9_M1BA0_1_G14") (pintype "bidirectional"))
    )
    (net (code "127") (name "unconnected-(U1B-IO_L38N_A4_M1CLKN_1-PadH11)") (class "Default")
      (node (ref "U1") (pin "H11") (pinfunction "IO_L38N_A4_M1CLKN_1_H11") (pintype "bidirectional"))
    )
    (net (code "128") (name "unconnected-(U1B-IO_L38P_A5_M1CLK_1-PadG12)") (class "Default")
      (node (ref "U1") (pin "G12") (pinfunction "IO_L38P_A5_M1CLK_1_G12") (pintype "bidirectional"))
    )
    (net (code "129") (name "unconnected-(U1B-IO_L39N_M1ODT_1-PadH14)") (class "Default")
      (node (ref "U1") (pin "H14") (pinfunction "IO_L39N_M1ODT_1_H14") (pintype "bidirectional"))
    )
    (net (code "130") (name "unconnected-(U1B-IO_L39P_M1A3_1-PadH13)") (class "Default")
      (node (ref "U1") (pin "H13") (pinfunction "IO_L39P_M1A3_1_H13") (pintype "bidirectional"))
    )
    (net (code "131") (name "unconnected-(U1B-IO_L40N_GCLK10_M1A6_1-PadJ12)") (class "Default")
      (node (ref "U1") (pin "J12") (pinfunction "IO_L40N_GCLK10_M1A6_1_J12") (pintype "bidirectional"))
    )
    (net (code "132") (name "unconnected-(U1B-IO_L40P_GCLK11_M1A5_1-PadJ11)") (class "Default")
      (node (ref "U1") (pin "J11") (pinfunction "IO_L40P_GCLK11_M1A5_1_J11") (pintype "bidirectional"))
    )
    (net (code "133") (name "unconnected-(U1B-IO_L41N_GCLK8_M1CASN_1-PadK14)") (class "Default")
      (node (ref "U1") (pin "K14") (pinfunction "IO_L41N_GCLK8_M1CASN_1_K14") (pintype "bidirectional"))
    )
    (net (code "134") (name "unconnected-(U1B-IO_L41P_GCLK9_IRDY1_M1RASN_1-PadJ13)") (class "Default")
      (node (ref "U1") (pin "J13") (pinfunction "IO_L41P_GCLK9_IRDY1_M1RASN_1_J13") (pintype "bidirectional"))
    )
    (net (code "135") (name "unconnected-(U1B-IO_L42N_GCLK6_TRDY1_M1LDM_1-PadK11)") (class "Default")
      (node (ref "U1") (pin "K11") (pinfunction "IO_L42N_GCLK6_TRDY1_M1LDM_1_K11") (pintype "bidirectional"))
    )
    (net (code "136") (name "unconnected-(U1B-IO_L42P_GCLK7_M1UDM_1-PadK12)") (class "Default")
      (node (ref "U1") (pin "K12") (pinfunction "IO_L42P_GCLK7_M1UDM_1_K12") (pintype "bidirectional"))
    )
    (net (code "137") (name "unconnected-(U1B-IO_L43P_GCLK5_M1DQ4_1-PadJ14)") (class "Default")
      (node (ref "U1") (pin "J14") (pinfunction "IO_L43P_GCLK5_M1DQ4_1_J14") (pintype "bidirectional"))
    )
    (net (code "138") (name "unconnected-(U1B-IO_L45P_A1_M1LDQS_1-PadN14)") (class "Default")
      (node (ref "U1") (pin "N14") (pinfunction "IO_L45P_A1_M1LDQS_1_N14") (pintype "bidirectional"))
    )
    (net (code "139") (name "unconnected-(U1B-IO_L47P_FWE_B_M1DQ0_1-PadL14)") (class "Default")
      (node (ref "U1") (pin "L14") (pinfunction "IO_L47P_FWE_B_M1DQ0_1_L14") (pintype "bidirectional"))
    )
    (net (code "140") (name "unconnected-(U1B-IO_L53N_VREF_1-PadL13)") (class "Default")
      (node (ref "U1") (pin "L13") (pinfunction "IO_L53N_VREF_1_L13") (pintype "bidirectional"))
    )
    (net (code "141") (name "unconnected-(U1B-IO_L53P_1-PadL12)") (class "Default")
      (node (ref "U1") (pin "L12") (pinfunction "IO_L53P_1_L12") (pintype "bidirectional"))
    )
    (net (code "142") (name "unconnected-(U1B-IO_L74N_DOUT_BUSY_1-PadM14)") (class "Default")
      (node (ref "U1") (pin "M14") (pinfunction "IO_L74N_DOUT_BUSY_1_M14") (pintype "bidirectional"))
    )
    (net (code "143") (name "unconnected-(U1B-IO_L74P_AWAKE_1-PadM13)") (class "Default")
      (node (ref "U1") (pin "M13") (pinfunction "IO_L74P_AWAKE_1_M13") (pintype "bidirectional"))
    )
    (net (code "144") (name "unconnected-(U1C-IO_L2N_CMPMOSI_2-PadM11)") (class "Default")
      (node (ref "U1") (pin "M11") (pinfunction "IO_L2N_CMPMOSI_2_M11") (pintype "bidirectional"))
    )
    (net (code "145") (name "unconnected-(U1C-IO_L2P_CMPCLK_2-PadM12)") (class "Default")
      (node (ref "U1") (pin "M12") (pinfunction "IO_L2P_CMPCLK_2_M12") (pintype "bidirectional"))
    )
    (net (code "146") (name "unconnected-(U1C-IO_L3N_MOSI_CSI_B_MISO0_2-PadT10)") (class "Default")
      (node (ref "U1") (pin "T10") (pinfunction "IO_L3N_MOSI_CSI_B_MISO0_2_T10") (pintype "bidirectional"))
    )
    (net (code "147") (name "unconnected-(U1C-IO_L3P_D0_DIN_MISO_MISO1_2-PadP10)") (class "Default")
      (node (ref "U1") (pin "P10") (pinfunction "IO_L3P_D0_DIN_MISO_MISO1_2_P10") (pintype "bidirectional"))
    )
    (net (code "148") (name "unconnected-(U1C-IO_L12N_D2_MISO3_2-PadP12)") (class "Default")
      (node (ref "U1") (pin "P12") (pinfunction "IO_L12N_D2_MISO3_2_P12") (pintype "bidirectional"))
    )
    (net (code "149") (name "unconnected-(U1C-IO_L12P_D1_MISO2_2-PadN12)") (class "Default")
      (node (ref "U1") (pin "N12") (pinfunction "IO_L12P_D1_MISO2_2_N12") (pintype "bidirectional"))
    )
    (net (code "150") (name "unconnected-(U1C-IO_L13N_D10_2-PadP11)") (class "Default")
      (node (ref "U1") (pin "P11") (pinfunction "IO_L13N_D10_2_P11") (pintype "bidirectional"))
    )
    (net (code "151") (name "unconnected-(U1C-IO_L13P_M1_2-PadN11)") (class "Default")
      (node (ref "U1") (pin "N11") (pinfunction "IO_L13P_M1_2_N11") (pintype "bidirectional"))
    )
    (net (code "152") (name "unconnected-(U1C-IO_L14N_D12_2-PadP9)") (class "Default")
      (node (ref "U1") (pin "P9") (pinfunction "IO_L14N_D12_2_P9") (pintype "bidirectional"))
    )
    (net (code "153") (name "unconnected-(U1C-IO_L14P_D11_2-PadN9)") (class "Default")
      (node (ref "U1") (pin "N9") (pinfunction "IO_L14P_D11_2_N9") (pintype "bidirectional"))
    )
    (net (code "154") (name "unconnected-(U1C-IO_L16N_VREF_2-PadM10)") (class "Default")
      (node (ref "U1") (pin "M10") (pinfunction "IO_L16N_VREF_2_M10") (pintype "bidirectional"))
    )
    (net (code "155") (name "unconnected-(U1C-IO_L16P_2-PadL10)") (class "Default")
      (node (ref "U1") (pin "L10") (pinfunction "IO_L16P_2_L10") (pintype "bidirectional"))
    )
    (net (code "156") (name "unconnected-(U1C-IO_L31N_GCLK30_D15_2-PadM7)") (class "Default")
      (node (ref "U1") (pin "M7") (pinfunction "IO_L31N_GCLK30_D15_2_M7") (pintype "bidirectional"))
    )
    (net (code "157") (name "unconnected-(U1C-IO_L31P_GCLK31_D14_2-PadP7)") (class "Default")
      (node (ref "U1") (pin "P7") (pinfunction "IO_L31P_GCLK31_D14_2_P7") (pintype "bidirectional"))
    )
    (net (code "158") (name "unconnected-(U1C-IO_L32N_GCLK28_2-PadT7)") (class "Default")
      (node (ref "U1") (pin "T7") (pinfunction "IO_L32N_GCLK28_2_T7") (pintype "bidirectional"))
    )
    (net (code "159") (name "unconnected-(U1C-IO_L32P_GCLK29_2-PadR7)") (class "Default")
      (node (ref "U1") (pin "R7") (pinfunction "IO_L32P_GCLK29_2_R7") (pintype "bidirectional"))
    )
    (net (code "160") (name "unconnected-(U1C-IO_L47N_2-PadT6)") (class "Default")
      (node (ref "U1") (pin "T6") (pinfunction "IO_L47N_2_T6") (pintype "bidirectional"))
    )
    (net (code "161") (name "unconnected-(U1C-IO_L47P_2-PadP6)") (class "Default")
      (node (ref "U1") (pin "P6") (pinfunction "IO_L47P_2_P6") (pintype "bidirectional"))
    )
    (net (code "162") (name "unconnected-(U1C-IO_L48N_RDWR_B_VREF_2-PadT5)") (class "Default")
      (node (ref "U1") (pin "T5") (pinfunction "IO_L48N_RDWR_B_VREF_2_T5") (pintype "bidirectional"))
    )
    (net (code "163") (name "unconnected-(U1C-IO_L48P_D7_2-PadR5)") (class "Default")
      (node (ref "U1") (pin "R5") (pinfunction "IO_L48P_D7_2_R5") (pintype "bidirectional"))
    )
    (net (code "164") (name "unconnected-(U1C-IO_L49N_D4_2-PadP5)") (class "Default")
      (node (ref "U1") (pin "P5") (pinfunction "IO_L49N_D4_2_P5") (pintype "bidirectional"))
    )
    (net (code "165") (name "unconnected-(U1C-IO_L49P_D3_2-PadN5)") (class "Default")
      (node (ref "U1") (pin "N5") (pinfunction "IO_L49P_D3_2_N5") (pintype "bidirectional"))
    )
    (net (code "166") (name "unconnected-(U1C-IO_L62N_D6_2-PadL7)") (class "Default")
      (node (ref "U1") (pin "L7") (pinfunction "IO_L62N_D6_2_L7") (pintype "bidirectional"))
    )
    (net (code "167") (name "unconnected-(U1C-IO_L62P_D5_2-PadL8)") (class "Default")
      (node (ref "U1") (pin "L8") (pinfunction "IO_L62P_D5_2_L8") (pintype "bidirectional"))
    )
    (net (code "168") (name "unconnected-(U1C-IO_L63N_2-PadT4)") (class "Default")
      (node (ref "U1") (pin "T4") (pinfunction "IO_L63N_2_T4") (pintype "bidirectional"))
    )
    (net (code "169") (name "unconnected-(U1C-IO_L63P_2-PadP4)") (class "Default")
      (node (ref "U1") (pin "P4") (pinfunction "IO_L63P_2_P4") (pintype "bidirectional"))
    )
    (net (code "170") (name "unconnected-(U1C-IO_L64N_D9_2-PadN6)") (class "Default")
      (node (ref "U1") (pin "N6") (pinfunction "IO_L64N_D9_2_N6") (pintype "bidirectional"))
    )
    (net (code "171") (name "unconnected-(U1C-IO_L64P_D8_2-PadM6)") (class "Default")
      (node (ref "U1") (pin "M6") (pinfunction "IO_L64P_D8_2_M6") (pintype "bidirectional"))
    )
    (net (code "172") (name "unconnected-(U1C-IO_L65N_CSO_B_2-PadT3)") (class "Default")
      (node (ref "U1") (pin "T3") (pinfunction "IO_L65N_CSO_B_2_T3") (pintype "bidirectional"))
    )
    (net (code "173") (name "unconnected-(U1C-IO_L65P_INIT_B_2-PadR3)") (class "Default")
      (node (ref "U1") (pin "R3") (pinfunction "IO_L65P_INIT_B_2_R3") (pintype "bidirectional"))
    )
    (net (code "174") (name "unconnected-(U1D-IO_L1N_VREF_3-PadM3)") (class "Default")
      (node (ref "U1") (pin "M3") (pinfunction "IO_L1N_VREF_3_M3") (pintype "bidirectional"))
    )
    (net (code "175") (name "unconnected-(U1D-IO_L1P_3-PadM4)") (class "Default")
      (node (ref "U1") (pin "M4") (pinfunction "IO_L1P_3_M4") (pintype "bidirectional"))
    )
    (net (code "176") (name "unconnected-(U1D-IO_L2N_3-PadN4)") (class "Default")
      (node (ref "U1") (pin "N4") (pinfunction "IO_L2N_3_N4") (pintype "bidirectional"))
    )
    (net (code "177") (name "unconnected-(U1D-IO_L2P_3-PadM5)") (class "Default")
      (node (ref "U1") (pin "M5") (pinfunction "IO_L2P_3_M5") (pintype "bidirectional"))
    )
    (net (code "178") (name "unconnected-(U1D-IO_L34P_M3UDQS_3-PadN3)") (class "Default")
      (node (ref "U1") (pin "N3") (pinfunction "IO_L34P_M3UDQS_3_N3") (pintype "bidirectional"))
    )
    (net (code "179") (name "unconnected-(U1D-IO_L42N_GCLK24_M3LDM_3-PadJ4)") (class "Default")
      (node (ref "U1") (pin "J4") (pinfunction "IO_L42N_GCLK24_M3LDM_3_J4") (pintype "bidirectional"))
    )
    (net (code "180") (name "unconnected-(U1D-IO_L43N_GCLK22_IRDY2_M3CASN_3-PadH5)") (class "Default")
      (node (ref "U1") (pin "H5") (pinfunction "IO_L43N_GCLK22_IRDY2_M3CASN_3_H5") (pintype "bidirectional"))
    )
    (net (code "181") (name "unconnected-(U1D-IO_L43P_GCLK23_M3RASN_3-PadJ6)") (class "Default")
      (node (ref "U1") (pin "J6") (pinfunction "IO_L43P_GCLK23_M3RASN_3_J6") (pintype "bidirectional"))
    )
    (net (code "182") (name "unconnected-(U1D-IO_L44P_GCLK21_M3A5_3-PadH4)") (class "Default")
      (node (ref "U1") (pin "H4") (pinfunction "IO_L44P_GCLK21_M3A5_3_H4") (pintype "bidirectional"))
    )
    (net (code "183") (name "unconnected-(U1D-IO_L45N_M3ODT_3-PadL5)") (class "Default")
      (node (ref "U1") (pin "L5") (pinfunction "IO_L45N_M3ODT_3_L5") (pintype "bidirectional"))
    )
    (net (code "184") (name "unconnected-(U1D-IO_L45P_M3A3_3-PadL4)") (class "Default")
      (node (ref "U1") (pin "L4") (pinfunction "IO_L45P_M3A3_3_L4") (pintype "bidirectional"))
    )
    (net (code "185") (name "unconnected-(U1D-IO_L47N_M3A1_3-PadK6)") (class "Default")
      (node (ref "U1") (pin "K6") (pinfunction "IO_L47N_M3A1_3_K6") (pintype "bidirectional"))
    )
    (net (code "186") (name "unconnected-(U1D-IO_L47P_M3A0_3-PadK5)") (class "Default")
      (node (ref "U1") (pin "K5") (pinfunction "IO_L47P_M3A0_3_K5") (pintype "bidirectional"))
    )
    (net (code "187") (name "unconnected-(U1D-IO_L51N_M3A4_3-PadG5)") (class "Default")
      (node (ref "U1") (pin "G5") (pinfunction "IO_L51N_M3A4_3_G5") (pintype "bidirectional"))
    )
    (net (code "188") (name "unconnected-(U1D-IO_L51P_M3A10_3-PadG6)") (class "Default")
      (node (ref "U1") (pin "G6") (pinfunction "IO_L51P_M3A10_3_G6") (pintype "bidirectional"))
    )
    (net (code "189") (name "unconnected-(U1D-IO_L52P_M3A8_3-PadB2)") (class "Default")
      (node (ref "U1") (pin "B2") (pinfunction "IO_L52P_M3A8_3_B2") (pintype "bidirectional"))
    )
    (net (code "190") (name "unconnected-(U1D-IO_L53P_M3CKE_3-PadF4)") (class "Default")
      (node (ref "U1") (pin "F4") (pinfunction "IO_L53P_M3CKE_3_F4") (pintype "bidirectional"))
    )
    (net (code "191") (name "unconnected-(U1D-IO_L54P_M3RESET_3-PadE4)") (class "Default")
      (node (ref "U1") (pin "E4") (pinfunction "IO_L54P_M3RESET_3_E4") (pintype "bidirectional"))
    )
    (net (code "192") (name "unconnected-(U1D-IO_L55N_M3A14_3-PadF5)") (class "Default")
      (node (ref "U1") (pin "F5") (pinfunction "IO_L55N_M3A14_3_F5") (pintype "bidirectional"))
    )
    (net (code "193") (name "unconnected-(U1D-IO_L55P_M3A13_3-PadF6)") (class "Default")
      (node (ref "U1") (pin "F6") (pinfunction "IO_L55P_M3A13_3_F6") (pintype "bidirectional"))
    )
    (net (code "194") (name "unconnected-(U1E-CMPCS_B_2-PadL11)") (class "Default")
      (node (ref "U1") (pin "L11") (pinfunction "CMPCS_B_2_L11") (pintype "input"))
    )
    (net (code "195") (name "unconnected-(U1E-DONE_2-PadP13)") (class "Default")
      (node (ref "U1") (pin "P13") (pinfunction "DONE_2_P13") (pintype "bidirectional"))
    )
    (net (code "196") (name "unconnected-(U1E-PROGRAM_B_2-PadT2)") (class "Default")
      (node (ref "U1") (pin "T2") (pinfunction "PROGRAM_B_2_T2") (pintype "input"))
    )
    (net (code "197") (name "unconnected-(U1E-SUSPEND-PadP14)") (class "Default")
      (node (ref "U1") (pin "P14") (pinfunction "SUSPEND_P14") (pintype "input"))
    )
  )
)
